# card.net
KiCad netlist of a schematic drawn in EAGLE
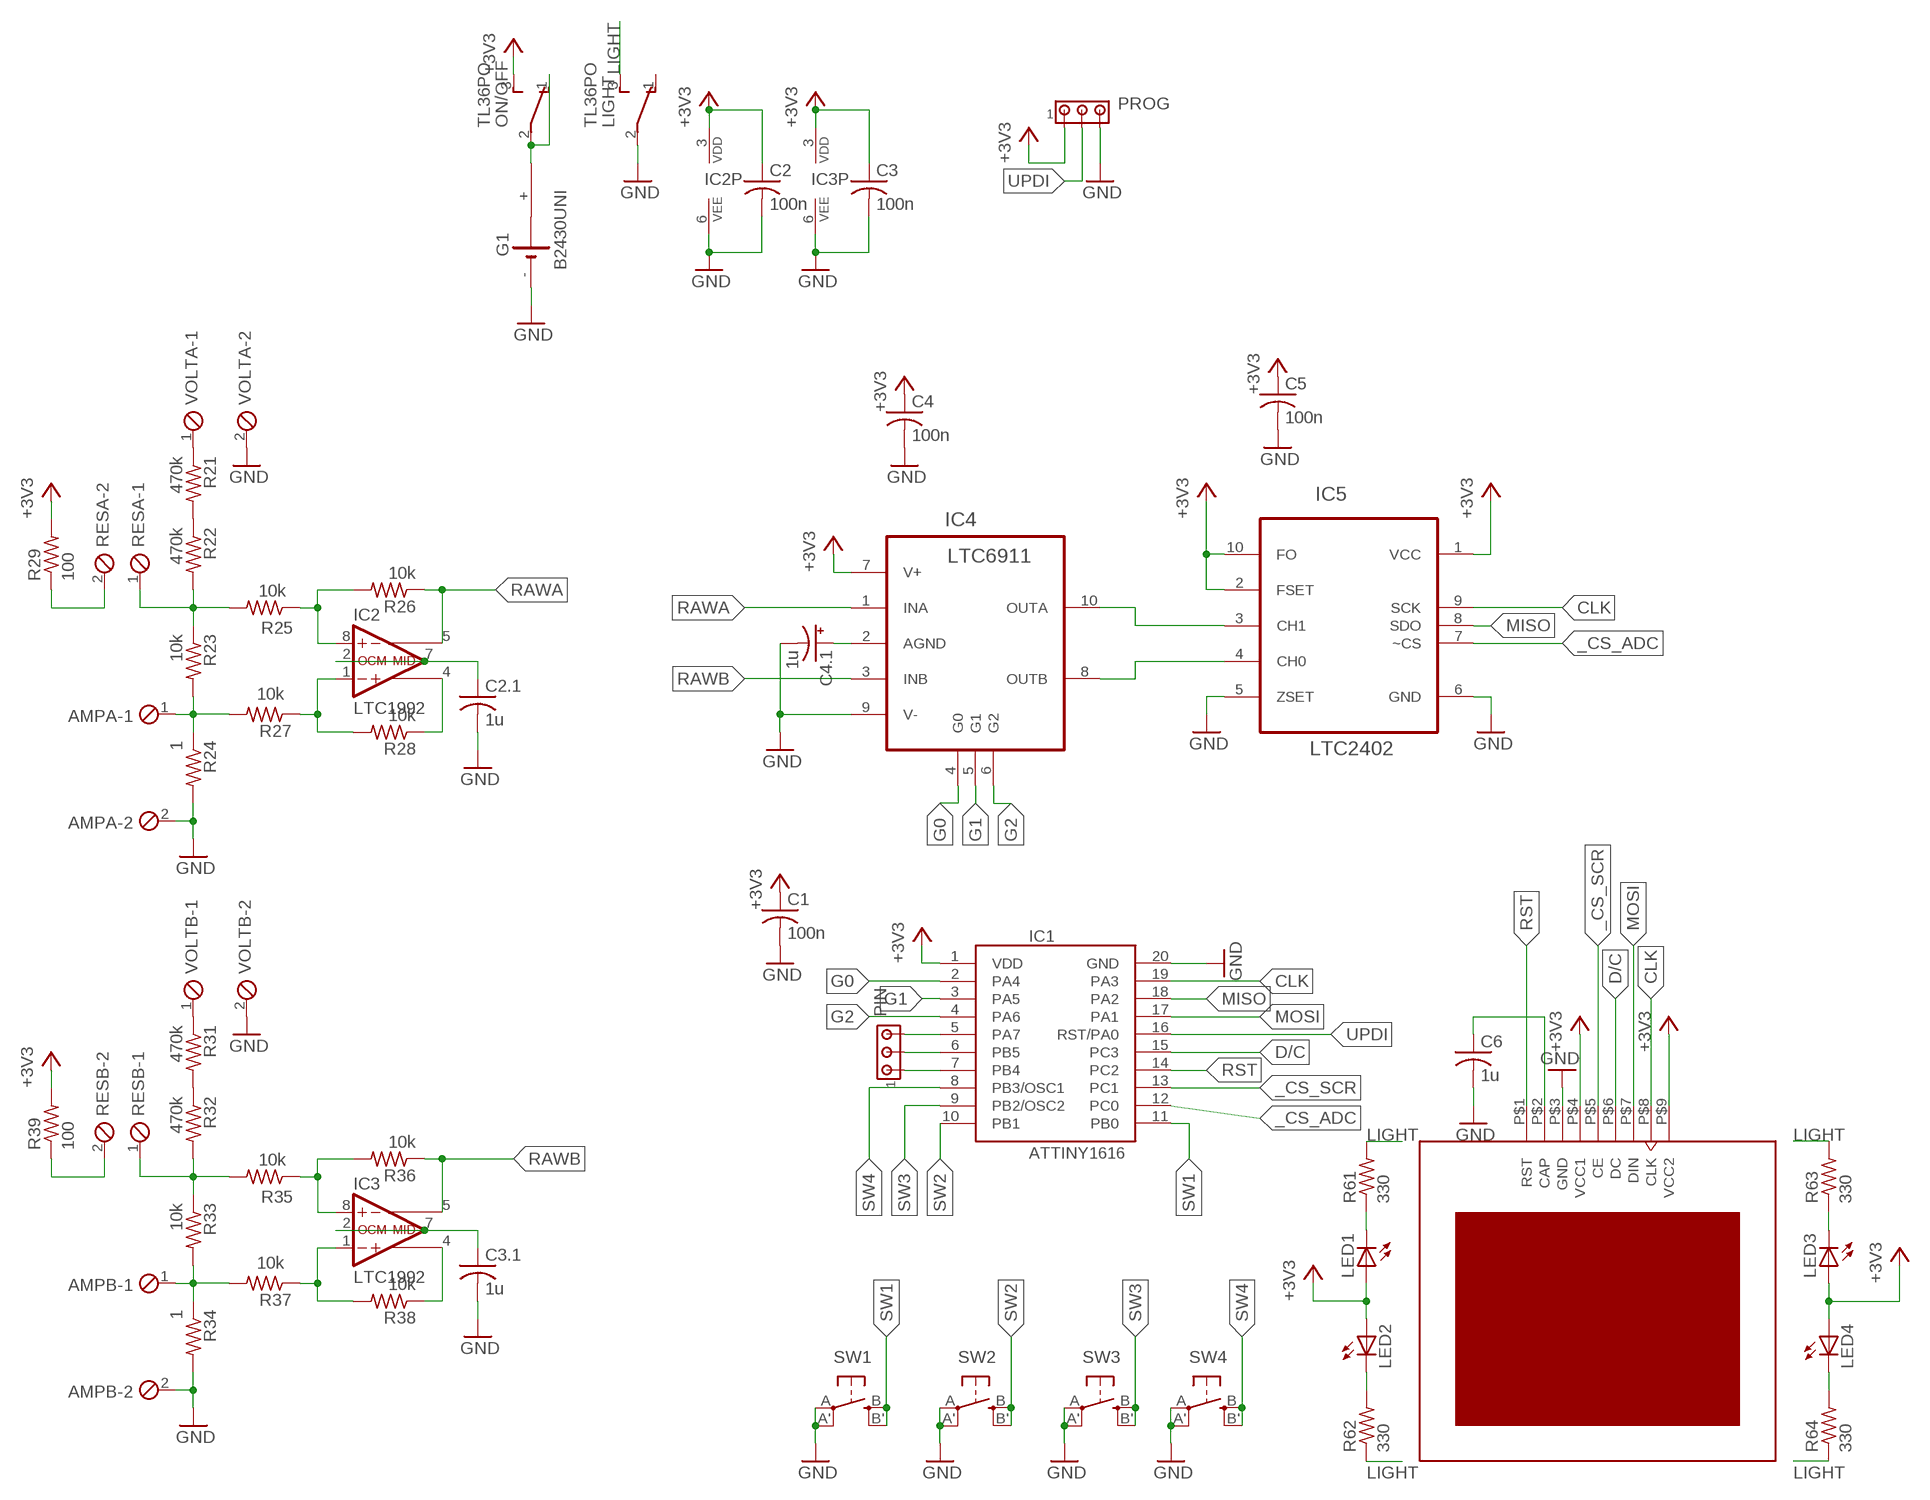
[diagram p0: schematic, sheet 1]

(export (version "E")
  (design (tool "Eeschema 10.0.6"))
  (components
    (comp (ref "AMPA")
      (value "MPT2")
      (footprint "eagle-import:2POL254")
      (libsource (lib "eagle-import") (part "MPT2"))
    )
    (comp (ref "AMPB")
      (value "MPT2")
      (footprint "eagle-import:2POL254")
      (libsource (lib "eagle-import") (part "MPT2"))
    )
    (comp (ref "C1")
      (value "100n")
      (footprint "eagle-import:C0805K")
      (libsource (lib "eagle-import") (part "C-USC0805K"))
    )
    (comp (ref "C2")
      (value "100n")
      (footprint "eagle-import:C0805K")
      (libsource (lib "eagle-import") (part "C-USC0805K"))
    )
    (comp (ref "C2.1")
      (value "1u")
      (footprint "eagle-import:C0805")
      (libsource (lib "eagle-import") (part "resistor_C-USC0805"))
    )
    (comp (ref "C3")
      (value "100n")
      (footprint "eagle-import:C0805K")
      (libsource (lib "eagle-import") (part "C-USC0805K"))
    )
    (comp (ref "C3.1")
      (value "1u")
      (footprint "eagle-import:C0805")
      (libsource (lib "eagle-import") (part "resistor_C-USC0805"))
    )
    (comp (ref "C4")
      (value "100n")
      (footprint "eagle-import:C0805K")
      (libsource (lib "eagle-import") (part "C-USC0805K"))
    )
    (comp (ref "C4.1")
      (value "1u")
      (footprint "eagle-import:A_3216-18R")
      (libsource (lib "eagle-import") (part "CPOL-USA/3216-18R"))
    )
    (comp (ref "C5")
      (value "100n")
      (footprint "eagle-import:C0805K")
      (libsource (lib "eagle-import") (part "C-USC0805K"))
    )
    (comp (ref "C6")
      (value "1u")
      (footprint "eagle-import:C0805")
      (libsource (lib "eagle-import") (part "resistor_C-USC0805"))
    )
    (comp (ref "G1")
      (value "B2430UNI")
      (footprint "eagle-import:B2430UNI")
      (libsource (lib "eagle-import") (part "B2430UNI"))
    )
    (comp (ref "IC1")
      (value "ATTINY1616")
      (footprint "eagle-import:SO20W")
      (libsource (lib "eagle-import") (part "ATTINY1616"))
    )
    (comp (ref "IC2")
      (value "LTC1992")
      (footprint "eagle-import:MSOP8")
      (libsource (lib "eagle-import") (part "LTC1992MS8C"))
    )
    (comp (ref "IC3")
      (value "LTC1992")
      (footprint "eagle-import:MSOP8")
      (libsource (lib "eagle-import") (part "LTC1992MS8C"))
    )
    (comp (ref "IC4")
      (value "LTC6911")
      (footprint "eagle-import:MSOP10")
      (libsource (lib "eagle-import") (part "LTC6911CMS-1"))
    )
    (comp (ref "IC5")
      (value "LTC2402")
      (footprint "eagle-import:MSOP10")
      (libsource (lib "eagle-import") (part "LTC2402CMS"))
    )
    (comp (ref "LED1")
      (value "LEDCHIP-LED0805")
      (footprint "eagle-import:CHIP-LED0805")
      (libsource (lib "eagle-import") (part "LEDCHIP-LED0805"))
    )
    (comp (ref "LED2")
      (value "LEDCHIP-LED0805")
      (footprint "eagle-import:CHIP-LED0805")
      (libsource (lib "eagle-import") (part "LEDCHIP-LED0805"))
    )
    (comp (ref "LED3")
      (value "LEDCHIP-LED0805")
      (footprint "eagle-import:CHIP-LED0805")
      (libsource (lib "eagle-import") (part "LEDCHIP-LED0805"))
    )
    (comp (ref "LED4")
      (value "LEDCHIP-LED0805")
      (footprint "eagle-import:CHIP-LED0805")
      (libsource (lib "eagle-import") (part "LEDCHIP-LED0805"))
    )
    (comp (ref "LIGHT")
      (value "TL36PO")
      (footprint "eagle-import:TL3XPO")
      (libsource (lib "eagle-import") (part "TL36PO"))
    )
    (comp (ref "ON/OFF")
      (value "TL36PO")
      (footprint "eagle-import:TL3XPO")
      (libsource (lib "eagle-import") (part "TL36PO"))
    )
    (comp (ref "PIN")
      (value "MTA03-100")
      (footprint "eagle-import:10X03MTA")
      (libsource (lib "eagle-import") (part "MTA03-100"))
    )
    (comp (ref "PROG")
      (value "MTA03-100")
      (footprint "eagle-import:10X03MTA")
      (libsource (lib "eagle-import") (part "MTA03-100"))
    )
    (comp (ref "R21")
      (value "470k")
      (footprint "eagle-import:M0805")
      (libsource (lib "eagle-import") (part "R-US_M0805"))
    )
    (comp (ref "R22")
      (value "470k")
      (footprint "eagle-import:M0805")
      (libsource (lib "eagle-import") (part "R-US_M0805"))
    )
    (comp (ref "R23")
      (value "10k")
      (footprint "eagle-import:M0805")
      (libsource (lib "eagle-import") (part "R-US_M0805"))
    )
    (comp (ref "R24")
      (value "1")
      (footprint "eagle-import:M0805")
      (libsource (lib "eagle-import") (part "R-US_M0805"))
    )
    (comp (ref "R25")
      (value "10k")
      (footprint "eagle-import:M0805")
      (libsource (lib "eagle-import") (part "R-US_M0805"))
    )
    (comp (ref "R26")
      (value "10k")
      (footprint "eagle-import:M0805")
      (libsource (lib "eagle-import") (part "R-US_M0805"))
    )
    (comp (ref "R27")
      (value "10k")
      (footprint "eagle-import:M0805")
      (libsource (lib "eagle-import") (part "R-US_M0805"))
    )
    (comp (ref "R28")
      (value "10k")
      (footprint "eagle-import:M0805")
      (libsource (lib "eagle-import") (part "R-US_M0805"))
    )
    (comp (ref "R29")
      (value "100")
      (footprint "eagle-import:M0805")
      (libsource (lib "eagle-import") (part "R-US_M0805"))
    )
    (comp (ref "R31")
      (value "470k")
      (footprint "eagle-import:M0805")
      (libsource (lib "eagle-import") (part "R-US_M0805"))
    )
    (comp (ref "R32")
      (value "470k")
      (footprint "eagle-import:M0805")
      (libsource (lib "eagle-import") (part "R-US_M0805"))
    )
    (comp (ref "R33")
      (value "10k")
      (footprint "eagle-import:M0805")
      (libsource (lib "eagle-import") (part "R-US_M0805"))
    )
    (comp (ref "R34")
      (value "1")
      (footprint "eagle-import:M0805")
      (libsource (lib "eagle-import") (part "R-US_M0805"))
    )
    (comp (ref "R35")
      (value "10k")
      (footprint "eagle-import:M0805")
      (libsource (lib "eagle-import") (part "R-US_M0805"))
    )
    (comp (ref "R36")
      (value "10k")
      (footprint "eagle-import:M0805")
      (libsource (lib "eagle-import") (part "R-US_M0805"))
    )
    (comp (ref "R37")
      (value "10k")
      (footprint "eagle-import:M0805")
      (libsource (lib "eagle-import") (part "R-US_M0805"))
    )
    (comp (ref "R38")
      (value "10k")
      (footprint "eagle-import:M0805")
      (libsource (lib "eagle-import") (part "R-US_M0805"))
    )
    (comp (ref "R39")
      (value "100")
      (footprint "eagle-import:M0805")
      (libsource (lib "eagle-import") (part "R-US_M0805"))
    )
    (comp (ref "R61")
      (value "330")
      (footprint "eagle-import:M0805")
      (libsource (lib "eagle-import") (part "R-US_M0805"))
    )
    (comp (ref "R62")
      (value "330")
      (footprint "eagle-import:M0805")
      (libsource (lib "eagle-import") (part "R-US_M0805"))
    )
    (comp (ref "R63")
      (value "330")
      (footprint "eagle-import:M0805")
      (libsource (lib "eagle-import") (part "R-US_M0805"))
    )
    (comp (ref "R64")
      (value "330")
      (footprint "eagle-import:M0805")
      (libsource (lib "eagle-import") (part "R-US_M0805"))
    )
    (comp (ref "RESA")
      (value "MPT2")
      (footprint "eagle-import:2POL254")
      (libsource (lib "eagle-import") (part "MPT2"))
    )
    (comp (ref "RESB")
      (value "MPT2")
      (footprint "eagle-import:2POL254")
      (libsource (lib "eagle-import") (part "MPT2"))
    )
    (comp (ref "SW1")
      (value "SPST_TACT-EVQQ2")
      (footprint "eagle-import:EVQ-Q2")
      (libsource (lib "eagle-import") (part "SPST_TACT-EVQQ2"))
    )
    (comp (ref "SW2")
      (value "SPST_TACT-EVQQ2")
      (footprint "eagle-import:EVQ-Q2")
      (libsource (lib "eagle-import") (part "SPST_TACT-EVQQ2"))
    )
    (comp (ref "SW3")
      (value "SPST_TACT-EVQQ2")
      (footprint "eagle-import:EVQ-Q2")
      (libsource (lib "eagle-import") (part "SPST_TACT-EVQQ2"))
    )
    (comp (ref "SW4")
      (value "SPST_TACT-EVQQ2")
      (footprint "eagle-import:EVQ-Q2")
      (libsource (lib "eagle-import") (part "SPST_TACT-EVQQ2"))
    )
    (comp (ref "U$1")
      (value "NOKIA_SCREEN")
      (footprint "eagle-import:NOKIA_SCREEN")
      (libsource (lib "eagle-import") (part "NOKIA_SCREEN"))
    )
    (comp (ref "VOLTA")
      (value "MPT2")
      (footprint "eagle-import:2POL254")
      (libsource (lib "eagle-import") (part "MPT2"))
    )
    (comp (ref "VOLTB")
      (value "MPT2")
      (footprint "eagle-import:2POL254")
      (libsource (lib "eagle-import") (part "MPT2"))
    )
  )
  (nets
    (net (code "1") (name "+3V3") (class "Default")
      (node (ref "C1") (pin "1") (pinfunction "1_1") (pintype "passive"))
      (node (ref "C2") (pin "1") (pinfunction "1_1") (pintype "passive"))
      (node (ref "C3") (pin "1") (pinfunction "1_1") (pintype "passive"))
      (node (ref "C4") (pin "1") (pinfunction "1_1") (pintype "passive"))
      (node (ref "C5") (pin "1") (pinfunction "1_1") (pintype "passive"))
      (node (ref "IC1") (pin "1") (pinfunction "VDD_1") (pintype "power_in"))
      (node (ref "IC2") (pin "3") (pinfunction "VDD_3") (pintype "power_in"))
      (node (ref "IC3") (pin "3") (pinfunction "VDD_3") (pintype "power_in"))
      (node (ref "IC4") (pin "7") (pinfunction "V+_7") (pintype "power_in"))
      (node (ref "IC5") (pin "1") (pinfunction "VCC_1") (pintype "power_in"))
      (node (ref "IC5") (pin "10") (pinfunction "FO_10") (pintype "input"))
      (node (ref "IC5") (pin "2") (pinfunction "FSET_2") (pintype "input"))
      (node (ref "LED1") (pin "A") (pinfunction "A_A") (pintype "passive"))
      (node (ref "LED2") (pin "A") (pinfunction "A_A") (pintype "passive"))
      (node (ref "LED3") (pin "A") (pinfunction "A_A") (pintype "passive"))
      (node (ref "LED4") (pin "A") (pinfunction "A_A") (pintype "passive"))
      (node (ref "ON/OFF") (pin "3") (pinfunction "S_3") (pintype "passive"))
      (node (ref "PROG") (pin "1") (pinfunction "1_1") (pintype "passive"))
      (node (ref "R29") (pin "2") (pinfunction "2_2") (pintype "passive"))
      (node (ref "R39") (pin "2") (pinfunction "2_2") (pintype "passive"))
      (node (ref "U$1") (pin "P$4") (pinfunction "VCC1_P$4") (pintype "power_in"))
      (node (ref "U$1") (pin "P$9") (pinfunction "VCC2_P$9") (pintype "power_in"))
    )
    (net (code "2") (name "/LIGHT") (class "Default")
      (node (ref "LIGHT") (pin "3") (pinfunction "S_3") (pintype "passive"))
      (node (ref "R61") (pin "2") (pinfunction "2_2") (pintype "passive"))
      (node (ref "R62") (pin "1") (pinfunction "1_1") (pintype "passive"))
      (node (ref "R63") (pin "2") (pinfunction "2_2") (pintype "passive"))
      (node (ref "R64") (pin "1") (pinfunction "1_1") (pintype "passive"))
    )
    (net (code "3") (name "CLK") (class "Default")
      (node (ref "IC1") (pin "19") (pinfunction "PA3_19") (pintype "bidirectional"))
      (node (ref "IC5") (pin "9") (pinfunction "SCK_9") (pintype "input"))
      (node (ref "U$1") (pin "P$8") (pinfunction "CLK_P$8") (pintype "input"))
    )
    (net (code "4") (name "D{slash}C") (class "Default")
      (node (ref "IC1") (pin "15") (pinfunction "PC3_15") (pintype "bidirectional"))
      (node (ref "U$1") (pin "P$6") (pinfunction "DC_P$6") (pintype "input"))
    )
    (net (code "5") (name "G0") (class "Default")
      (node (ref "IC1") (pin "2") (pinfunction "PA4_2") (pintype "bidirectional"))
      (node (ref "IC4") (pin "4") (pinfunction "G0_4") (pintype "input"))
    )
    (net (code "6") (name "G1") (class "Default")
      (node (ref "IC1") (pin "3") (pinfunction "PA5_3") (pintype "bidirectional"))
      (node (ref "IC4") (pin "5") (pinfunction "G1_5") (pintype "input"))
    )
    (net (code "7") (name "G2") (class "Default")
      (node (ref "IC1") (pin "4") (pinfunction "PA6_4") (pintype "bidirectional"))
      (node (ref "IC4") (pin "6") (pinfunction "G2_6") (pintype "input"))
    )
    (net (code "8") (name "GND") (class "Default")
      (node (ref "AMPA") (pin "2") (pinfunction "1_2") (pintype "passive"))
      (node (ref "AMPB") (pin "2") (pinfunction "1_2") (pintype "passive"))
      (node (ref "C1") (pin "2") (pinfunction "2_2") (pintype "passive"))
      (node (ref "C2") (pin "2") (pinfunction "2_2") (pintype "passive"))
      (node (ref "C2.1") (pin "2") (pinfunction "2_2") (pintype "passive"))
      (node (ref "C3") (pin "2") (pinfunction "2_2") (pintype "passive"))
      (node (ref "C3.1") (pin "2") (pinfunction "2_2") (pintype "passive"))
      (node (ref "C4") (pin "2") (pinfunction "2_2") (pintype "passive"))
      (node (ref "C4.1") (pin "-") (pinfunction "-_-") (pintype "passive"))
      (node (ref "C5") (pin "2") (pinfunction "2_2") (pintype "passive"))
      (node (ref "C6") (pin "2") (pinfunction "2_2") (pintype "passive"))
      (node (ref "G1") (pin "-") (pinfunction "-_-") (pintype "passive"))
      (node (ref "IC1") (pin "20") (pinfunction "GND_20") (pintype "power_in"))
      (node (ref "IC2") (pin "6") (pinfunction "VEE_6") (pintype "power_in"))
      (node (ref "IC3") (pin "6") (pinfunction "VEE_6") (pintype "power_in"))
      (node (ref "IC4") (pin "9") (pinfunction "V-_9") (pintype "power_in"))
      (node (ref "IC5") (pin "5") (pinfunction "ZSET_5") (pintype "input"))
      (node (ref "IC5") (pin "6") (pinfunction "GND_6") (pintype "passive"))
      (node (ref "LIGHT") (pin "2") (pinfunction "P_2") (pintype "passive"))
      (node (ref "PROG") (pin "3") (pinfunction "3_3") (pintype "passive"))
      (node (ref "R24") (pin "2") (pinfunction "2_2") (pintype "passive"))
      (node (ref "R34") (pin "2") (pinfunction "2_2") (pintype "passive"))
      (node (ref "SW1") (pin "A") (pinfunction "P_A") (pintype "passive"))
      (node (ref "SW1") (pin "A'") (pinfunction "P1_A'") (pintype "passive"))
      (node (ref "SW2") (pin "A") (pinfunction "P_A") (pintype "passive"))
      (node (ref "SW2") (pin "A'") (pinfunction "P1_A'") (pintype "passive"))
      (node (ref "SW3") (pin "A") (pinfunction "P_A") (pintype "passive"))
      (node (ref "SW3") (pin "A'") (pinfunction "P1_A'") (pintype "passive"))
      (node (ref "SW4") (pin "A") (pinfunction "P_A") (pintype "passive"))
      (node (ref "SW4") (pin "A'") (pinfunction "P1_A'") (pintype "passive"))
      (node (ref "U$1") (pin "P$3") (pinfunction "GND_P$3") (pintype "power_in"))
      (node (ref "VOLTA") (pin "2") (pinfunction "1_2") (pintype "passive"))
      (node (ref "VOLTB") (pin "2") (pinfunction "1_2") (pintype "passive"))
    )
    (net (code "9") (name "MISO") (class "Default")
      (node (ref "IC1") (pin "18") (pinfunction "PA2_18") (pintype "bidirectional"))
      (node (ref "IC5") (pin "8") (pinfunction "SDO_8") (pintype "output"))
    )
    (net (code "10") (name "MOSI") (class "Default")
      (node (ref "IC1") (pin "17") (pinfunction "PA1_17") (pintype "bidirectional"))
      (node (ref "U$1") (pin "P$7") (pinfunction "DIN_P$7") (pintype "input"))
    )
    (net (code "11") (name "Net-(AMPA-Pad1)") (class "Default")
      (node (ref "AMPA") (pin "1") (pinfunction "1_1") (pintype "passive"))
      (node (ref "R23") (pin "2") (pinfunction "2_2") (pintype "passive"))
      (node (ref "R24") (pin "1") (pinfunction "1_1") (pintype "passive"))
      (node (ref "R27") (pin "2") (pinfunction "2_2") (pintype "passive"))
    )
    (net (code "12") (name "Net-(AMPB-Pad1)") (class "Default")
      (node (ref "AMPB") (pin "1") (pinfunction "1_1") (pintype "passive"))
      (node (ref "R33") (pin "2") (pinfunction "2_2") (pintype "passive"))
      (node (ref "R34") (pin "1") (pinfunction "1_1") (pintype "passive"))
      (node (ref "R37") (pin "2") (pinfunction "2_2") (pintype "passive"))
    )
    (net (code "13") (name "Net-(IC1-PA7)") (class "Default")
      (node (ref "IC1") (pin "5") (pinfunction "PA7_5") (pintype "bidirectional"))
      (node (ref "PIN") (pin "3") (pinfunction "3_3") (pintype "passive"))
    )
    (net (code "14") (name "Net-(IC1-PB4)") (class "Default")
      (node (ref "IC1") (pin "7") (pinfunction "PB4_7") (pintype "bidirectional"))
      (node (ref "PIN") (pin "1") (pinfunction "1_1") (pintype "passive"))
    )
    (net (code "15") (name "Net-(IC1-PB5)") (class "Default")
      (node (ref "IC1") (pin "6") (pinfunction "PB5_6") (pintype "bidirectional"))
      (node (ref "PIN") (pin "2") (pinfunction "2_2") (pintype "passive"))
    )
    (net (code "16") (name "Net-(IC2A-+IN)") (class "Default")
      (node (ref "IC2") (pin "8") (pinfunction "+IN_8") (pintype "input"))
      (node (ref "R25") (pin "1") (pinfunction "1_1") (pintype "passive"))
      (node (ref "R26") (pin "2") (pinfunction "2_2") (pintype "passive"))
    )
    (net (code "17") (name "Net-(IC2A-+OUT)") (class "Default")
      (node (ref "IC2") (pin "4") (pinfunction "+OUT_4") (pintype "output"))
      (node (ref "R28") (pin "1") (pinfunction "1_1") (pintype "passive"))
    )
    (net (code "18") (name "Net-(IC2A--IN)") (class "Default")
      (node (ref "IC2") (pin "1") (pinfunction "-IN_1") (pintype "input"))
      (node (ref "R27") (pin "1") (pinfunction "1_1") (pintype "passive"))
      (node (ref "R28") (pin "2") (pinfunction "2_2") (pintype "passive"))
    )
    (net (code "19") (name "Net-(IC2A-MID)") (class "Default")
      (node (ref "C2.1") (pin "1") (pinfunction "1_1") (pintype "passive"))
      (node (ref "IC2") (pin "2") (pinfunction "OCM_2") (pintype "input"))
      (node (ref "IC2") (pin "7") (pinfunction "MID_7") (pintype "passive"))
    )
    (net (code "20") (name "Net-(IC3A-+IN)") (class "Default")
      (node (ref "IC3") (pin "8") (pinfunction "+IN_8") (pintype "input"))
      (node (ref "R35") (pin "1") (pinfunction "1_1") (pintype "passive"))
      (node (ref "R36") (pin "2") (pinfunction "2_2") (pintype "passive"))
    )
    (net (code "21") (name "Net-(IC3A-+OUT)") (class "Default")
      (node (ref "IC3") (pin "4") (pinfunction "+OUT_4") (pintype "output"))
      (node (ref "R38") (pin "1") (pinfunction "1_1") (pintype "passive"))
    )
    (net (code "22") (name "Net-(IC3A--IN)") (class "Default")
      (node (ref "IC3") (pin "1") (pinfunction "-IN_1") (pintype "input"))
      (node (ref "R37") (pin "1") (pinfunction "1_1") (pintype "passive"))
      (node (ref "R38") (pin "2") (pinfunction "2_2") (pintype "passive"))
    )
    (net (code "23") (name "Net-(IC3A-MID)") (class "Default")
      (node (ref "C3.1") (pin "1") (pinfunction "1_1") (pintype "passive"))
      (node (ref "IC3") (pin "2") (pinfunction "OCM_2") (pintype "input"))
      (node (ref "IC3") (pin "7") (pinfunction "MID_7") (pintype "passive"))
    )
    (net (code "24") (name "Net-(IC4-AGND)") (class "Default")
      (node (ref "C4.1") (pin "+") (pinfunction "+_+") (pintype "passive"))
      (node (ref "IC4") (pin "2") (pinfunction "AGND_2") (pintype "passive"))
    )
    (net (code "25") (name "Net-(IC4-OUTA)") (class "Default")
      (node (ref "IC4") (pin "10") (pinfunction "OUTA_10") (pintype "output"))
      (node (ref "IC5") (pin "3") (pinfunction "CH1_3") (pintype "input"))
    )
    (net (code "26") (name "Net-(IC4-OUTB)") (class "Default")
      (node (ref "IC4") (pin "8") (pinfunction "OUTB_8") (pintype "output"))
      (node (ref "IC5") (pin "4") (pinfunction "CH0_4") (pintype "input"))
    )
    (net (code "27") (name "Net-(LED1-PadC)") (class "Default")
      (node (ref "LED1") (pin "C") (pinfunction "C_C") (pintype "passive"))
      (node (ref "R61") (pin "1") (pinfunction "1_1") (pintype "passive"))
    )
    (net (code "28") (name "Net-(LED2-PadC)") (class "Default")
      (node (ref "LED2") (pin "C") (pinfunction "C_C") (pintype "passive"))
      (node (ref "R62") (pin "2") (pinfunction "2_2") (pintype "passive"))
    )
    (net (code "29") (name "Net-(LED3-PadC)") (class "Default")
      (node (ref "LED3") (pin "C") (pinfunction "C_C") (pintype "passive"))
      (node (ref "R63") (pin "1") (pinfunction "1_1") (pintype "passive"))
    )
    (net (code "30") (name "Net-(LED4-PadC)") (class "Default")
      (node (ref "LED4") (pin "C") (pinfunction "C_C") (pintype "passive"))
      (node (ref "R64") (pin "2") (pinfunction "2_2") (pintype "passive"))
    )
    (net (code "31") (name "Net-(ON/OFF-O)") (class "Default")
      (node (ref "G1") (pin "+") (pinfunction "+_+") (pintype "passive"))
      (node (ref "ON/OFF") (pin "1") (pinfunction "O_1") (pintype "passive"))
      (node (ref "ON/OFF") (pin "2") (pinfunction "P_2") (pintype "passive"))
    )
    (net (code "32") (name "Net-(R21-Pad1)") (class "Default")
      (node (ref "R21") (pin "1") (pinfunction "1_1") (pintype "passive"))
      (node (ref "VOLTA") (pin "1") (pinfunction "1_1") (pintype "passive"))
    )
    (net (code "33") (name "Net-(R21-Pad2)") (class "Default")
      (node (ref "R21") (pin "2") (pinfunction "2_2") (pintype "passive"))
      (node (ref "R22") (pin "1") (pinfunction "1_1") (pintype "passive"))
    )
    (net (code "34") (name "Net-(R22-Pad2)") (class "Default")
      (node (ref "R22") (pin "2") (pinfunction "2_2") (pintype "passive"))
      (node (ref "R23") (pin "1") (pinfunction "1_1") (pintype "passive"))
      (node (ref "R25") (pin "2") (pinfunction "2_2") (pintype "passive"))
      (node (ref "RESA") (pin "1") (pinfunction "1_1") (pintype "passive"))
    )
    (net (code "35") (name "Net-(R31-Pad1)") (class "Default")
      (node (ref "R31") (pin "1") (pinfunction "1_1") (pintype "passive"))
      (node (ref "VOLTB") (pin "1") (pinfunction "1_1") (pintype "passive"))
    )
    (net (code "36") (name "Net-(R31-Pad2)") (class "Default")
      (node (ref "R31") (pin "2") (pinfunction "2_2") (pintype "passive"))
      (node (ref "R32") (pin "1") (pinfunction "1_1") (pintype "passive"))
    )
    (net (code "37") (name "Net-(R32-Pad2)") (class "Default")
      (node (ref "R32") (pin "2") (pinfunction "2_2") (pintype "passive"))
      (node (ref "R33") (pin "1") (pinfunction "1_1") (pintype "passive"))
      (node (ref "R35") (pin "2") (pinfunction "2_2") (pintype "passive"))
      (node (ref "RESB") (pin "1") (pinfunction "1_1") (pintype "passive"))
    )
    (net (code "38") (name "Net-(RESAB-1)") (class "Default")
      (node (ref "R29") (pin "1") (pinfunction "1_1") (pintype "passive"))
      (node (ref "RESA") (pin "2") (pinfunction "1_2") (pintype "passive"))
    )
    (net (code "39") (name "Net-(RESBB-1)") (class "Default")
      (node (ref "R39") (pin "1") (pinfunction "1_1") (pintype "passive"))
      (node (ref "RESB") (pin "2") (pinfunction "1_2") (pintype "passive"))
    )
    (net (code "40") (name "Net-(U$1-CAP)") (class "Default")
      (node (ref "C6") (pin "1") (pinfunction "1_1") (pintype "passive"))
      (node (ref "U$1") (pin "P$2") (pinfunction "CAP_P$2") (pintype "passive"))
    )
    (net (code "41") (name "RAWA") (class "Default")
      (node (ref "IC2") (pin "5") (pinfunction "-OUT_5") (pintype "output"))
      (node (ref "IC4") (pin "1") (pinfunction "INA_1") (pintype "input"))
      (node (ref "R26") (pin "1") (pinfunction "1_1") (pintype "passive"))
    )
    (net (code "42") (name "RAWB") (class "Default")
      (node (ref "IC3") (pin "5") (pinfunction "-OUT_5") (pintype "output"))
      (node (ref "IC4") (pin "3") (pinfunction "INB_3") (pintype "input"))
      (node (ref "R36") (pin "1") (pinfunction "1_1") (pintype "passive"))
    )
    (net (code "43") (name "RST") (class "Default")
      (node (ref "IC1") (pin "14") (pinfunction "PC2_14") (pintype "bidirectional"))
      (node (ref "U$1") (pin "P$1") (pinfunction "RST_P$1") (pintype "input"))
    )
    (net (code "44") (name "SW1") (class "Default")
      (node (ref "IC1") (pin "11") (pinfunction "PB0_11") (pintype "bidirectional"))
      (node (ref "SW1") (pin "B") (pinfunction "S_B") (pintype "passive"))
      (node (ref "SW1") (pin "B'") (pinfunction "S1_B'") (pintype "passive"))
    )
    (net (code "45") (name "SW2") (class "Default")
      (node (ref "IC1") (pin "10") (pinfunction "PB1_10") (pintype "bidirectional"))
      (node (ref "SW2") (pin "B") (pinfunction "S_B") (pintype "passive"))
      (node (ref "SW2") (pin "B'") (pinfunction "S1_B'") (pintype "passive"))
    )
    (net (code "46") (name "SW3") (class "Default")
      (node (ref "IC1") (pin "9") (pinfunction "PB2/OSC2_9") (pintype "bidirectional"))
      (node (ref "SW3") (pin "B") (pinfunction "S_B") (pintype "passive"))
      (node (ref "SW3") (pin "B'") (pinfunction "S1_B'") (pintype "passive"))
    )
    (net (code "47") (name "SW4") (class "Default")
      (node (ref "IC1") (pin "8") (pinfunction "PB3/OSC1_8") (pintype "bidirectional"))
      (node (ref "SW4") (pin "B") (pinfunction "S_B") (pintype "passive"))
      (node (ref "SW4") (pin "B'") (pinfunction "S1_B'") (pintype "passive"))
    )
    (net (code "48") (name "UPDI") (class "Default")
      (node (ref "IC1") (pin "16") (pinfunction "RST/PA0_16") (pintype "bidirectional"))
      (node (ref "PROG") (pin "2") (pinfunction "2_2") (pintype "passive"))
    )
    (net (code "49") (name "_CS_ADC") (class "Default")
      (node (ref "IC1") (pin "12") (pinfunction "PC0_12") (pintype "bidirectional"))
      (node (ref "IC5") (pin "7") (pinfunction "~{CS}_7") (pintype "input"))
    )
    (net (code "50") (name "_CS_SCR") (class "Default")
      (node (ref "IC1") (pin "13") (pinfunction "PC1_13") (pintype "bidirectional"))
      (node (ref "U$1") (pin "P$5") (pinfunction "CE_P$5") (pintype "input"))
    )
    (net (code "51") (name "unconnected-(G1-+-Pad+@1)") (class "Default")
      (node (ref "G1") (pin "+@1") (pinfunction "+_+@1") (pintype "passive"))
    )
    (net (code "52") (name "unconnected-(G1-+-Pad+@2)") (class "Default")
      (node (ref "G1") (pin "+@2") (pinfunction "+_+@2") (pintype "passive"))
    )
    (net (code "53") (name "unconnected-(G1-+-Pad+@3)") (class "Default")
      (node (ref "G1") (pin "+@3") (pinfunction "+_+@3") (pintype "passive"))
    )
    (net (code "54") (name "unconnected-(G1-+-Pad+@4)") (class "Default")
      (node (ref "G1") (pin "+@4") (pinfunction "+_+@4") (pintype "passive"))
    )
    (net (code "55") (name "unconnected-(G1---Pad-@1)") (class "Default")
      (node (ref "G1") (pin "-@1") (pinfunction "-_-@1") (pintype "passive"))
    )
    (net (code "56") (name "unconnected-(LIGHT-O-Pad1)") (class "Default")
      (node (ref "LIGHT") (pin "1") (pinfunction "O_1") (pintype "passive"))
    )
  )
)
